# Bf706_DSP.net
KiCad netlist of a schematic drawn in Altium Designer
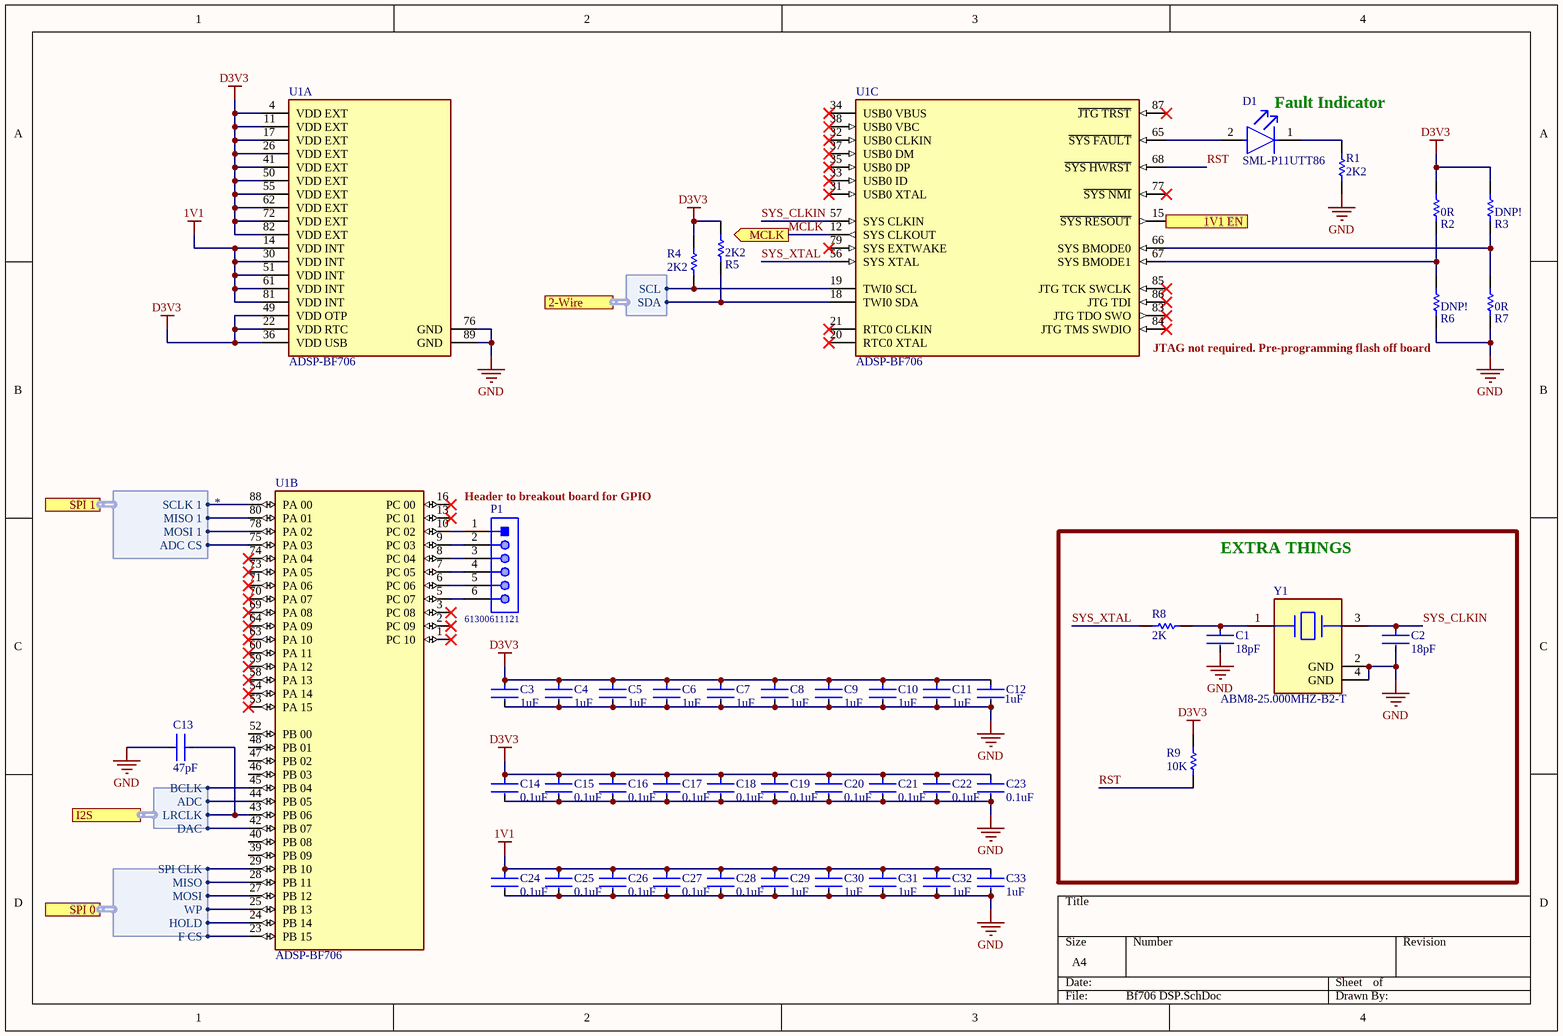
[diagram p0: Bf706 DSP.SchDoc]

(export (version "E")
  (design (tool "Eeschema 10.0.6"))
  (components
    (comp (ref "C1")
      (value "18pF")
      (footprint "FP-GRM15-MFG")
      (description "CAP CER 0.1UF 16V X7R 0402")
      (fields (field (name "MANUFACTURER PART NUMBER") "GRM155R71C104KA88D") (field (name "TOLERANCE") "10%"))
      (libsource (lib "Altium Content Vault") (part "236180d848d6139a670b325ea6854c9"))
    )
    (comp (ref "C2")
      (value "18pF")
      (footprint "FP-GRM15-MFG")
      (description "CAP CER 0.1UF 16V X7R 0402")
      (fields (field (name "MANUFACTURER PART NUMBER") "GRM155R71C104KA88D") (field (name "TOLERANCE") "10%"))
      (libsource (lib "Altium Content Vault") (part "236180d848d6139a670b325ea6854c9"))
    )
    (comp (ref "C3")
      (value "1uF")
      (footprint "FP-GRM15-MFG")
      (description "CAP CER 0.1UF 16V X7R 0402")
      (fields (field (name "MANUFACTURER PART NUMBER") "GRM155R71C104KA88D") (field (name "TOLERANCE") "10%"))
      (libsource (lib "Altium Content Vault") (part "236180d848d6139a670b325ea6854c9"))
    )
    (comp (ref "C4")
      (value "1uF")
      (footprint "FP-GRM15-MFG")
      (description "CAP CER 0.1UF 16V X7R 0402")
      (fields (field (name "MANUFACTURER PART NUMBER") "GRM155R71C104KA88D") (field (name "TOLERANCE") "10%"))
      (libsource (lib "Altium Content Vault") (part "236180d848d6139a670b325ea6854c9"))
    )
    (comp (ref "C5")
      (value "1uF")
      (footprint "FP-GRM15-MFG")
      (description "CAP CER 0.1UF 16V X7R 0402")
      (fields (field (name "MANUFACTURER PART NUMBER") "GRM155R71C104KA88D") (field (name "TOLERANCE") "10%"))
      (libsource (lib "Altium Content Vault") (part "236180d848d6139a670b325ea6854c9"))
    )
    (comp (ref "C6")
      (value "1uF")
      (footprint "FP-GRM15-MFG")
      (description "CAP CER 0.1UF 16V X7R 0402")
      (fields (field (name "MANUFACTURER PART NUMBER") "GRM155R71C104KA88D") (field (name "TOLERANCE") "10%"))
      (libsource (lib "Altium Content Vault") (part "236180d848d6139a670b325ea6854c9"))
    )
    (comp (ref "C7")
      (value "1uF")
      (footprint "FP-GRM15-MFG")
      (description "CAP CER 0.1UF 16V X7R 0402")
      (fields (field (name "MANUFACTURER PART NUMBER") "GRM155R71C104KA88D") (field (name "TOLERANCE") "10%"))
      (libsource (lib "Altium Content Vault") (part "236180d848d6139a670b325ea6854c9"))
    )
    (comp (ref "C8")
      (value "1uF")
      (footprint "FP-GRM15-MFG")
      (description "CAP CER 0.1UF 16V X7R 0402")
      (fields (field (name "MANUFACTURER PART NUMBER") "GRM155R71C104KA88D") (field (name "TOLERANCE") "10%"))
      (libsource (lib "Altium Content Vault") (part "236180d848d6139a670b325ea6854c9"))
    )
    (comp (ref "C9")
      (value "1uF")
      (footprint "FP-GRM15-MFG")
      (description "CAP CER 0.1UF 16V X7R 0402")
      (fields (field (name "MANUFACTURER PART NUMBER") "GRM155R71C104KA88D") (field (name "TOLERANCE") "10%"))
      (libsource (lib "Altium Content Vault") (part "236180d848d6139a670b325ea6854c9"))
    )
    (comp (ref "C10")
      (value "1uF")
      (footprint "FP-GRM15-MFG")
      (description "CAP CER 0.1UF 16V X7R 0402")
      (fields (field (name "MANUFACTURER PART NUMBER") "GRM155R71C104KA88D") (field (name "TOLERANCE") "10%"))
      (libsource (lib "Altium Content Vault") (part "236180d848d6139a670b325ea6854c9"))
    )
    (comp (ref "C11")
      (value "1uF")
      (footprint "FP-GRM15-MFG")
      (description "CAP CER 0.1UF 16V X7R 0402")
      (fields (field (name "MANUFACTURER PART NUMBER") "GRM155R71C104KA88D") (field (name "TOLERANCE") "10%"))
      (libsource (lib "Altium Content Vault") (part "236180d848d6139a670b325ea6854c9"))
    )
    (comp (ref "C12")
      (value "1uF")
      (footprint "FP-GRM15-MFG")
      (description "CAP CER 0.1UF 16V X7R 0402")
      (fields (field (name "MANUFACTURER PART NUMBER") "GRM155R71C104KA88D") (field (name "TOLERANCE") "10%"))
      (libsource (lib "Altium Content Vault") (part "236180d848d6139a670b325ea6854c9"))
    )
    (comp (ref "C13")
      (value "47pF")
      (footprint "FP-GRM15-MFG")
      (description "CAP CER 0.1UF 16V X7R 0402")
      (fields (field (name "MANUFACTURER PART NUMBER") "GRM155R71C104KA88D") (field (name "TOLERANCE") "10%"))
      (libsource (lib "Altium Content Vault") (part "236180d848d6139a670b325ea6854c9"))
    )
    (comp (ref "C14")
      (value "0.1uF")
      (footprint "FP-GRM15-MFG")
      (description "CAP CER 0.1UF 16V X7R 0402")
      (fields (field (name "MANUFACTURER PART NUMBER") "GRM155R71C104KA88D") (field (name "TOLERANCE") "10%"))
      (libsource (lib "Altium Content Vault") (part "236180d848d6139a670b325ea6854c9"))
    )
    (comp (ref "C15")
      (value "0.1uF")
      (footprint "FP-GRM15-MFG")
      (description "CAP CER 0.1UF 16V X7R 0402")
      (fields (field (name "MANUFACTURER PART NUMBER") "GRM155R71C104KA88D") (field (name "TOLERANCE") "10%"))
      (libsource (lib "Altium Content Vault") (part "236180d848d6139a670b325ea6854c9"))
    )
    (comp (ref "C16")
      (value "0.1uF")
      (footprint "FP-GRM15-MFG")
      (description "CAP CER 0.1UF 16V X7R 0402")
      (fields (field (name "MANUFACTURER PART NUMBER") "GRM155R71C104KA88D") (field (name "TOLERANCE") "10%"))
      (libsource (lib "Altium Content Vault") (part "236180d848d6139a670b325ea6854c9"))
    )
    (comp (ref "C17")
      (value "0.1uF")
      (footprint "FP-GRM15-MFG")
      (description "CAP CER 0.1UF 16V X7R 0402")
      (fields (field (name "MANUFACTURER PART NUMBER") "GRM155R71C104KA88D") (field (name "TOLERANCE") "10%"))
      (libsource (lib "Altium Content Vault") (part "236180d848d6139a670b325ea6854c9"))
    )
    (comp (ref "C18")
      (value "0.1uF")
      (footprint "FP-GRM15-MFG")
      (description "CAP CER 0.1UF 16V X7R 0402")
      (fields (field (name "MANUFACTURER PART NUMBER") "GRM155R71C104KA88D") (field (name "TOLERANCE") "10%"))
      (libsource (lib "Altium Content Vault") (part "236180d848d6139a670b325ea6854c9"))
    )
    (comp (ref "C19")
      (value "0.1uF")
      (footprint "FP-GRM15-MFG")
      (description "CAP CER 0.1UF 16V X7R 0402")
      (fields (field (name "MANUFACTURER PART NUMBER") "GRM155R71C104KA88D") (field (name "TOLERANCE") "10%"))
      (libsource (lib "Altium Content Vault") (part "236180d848d6139a670b325ea6854c9"))
    )
    (comp (ref "C20")
      (value "0.1uF")
      (footprint "FP-GRM15-MFG")
      (description "CAP CER 0.1UF 16V X7R 0402")
      (fields (field (name "MANUFACTURER PART NUMBER") "GRM155R71C104KA88D") (field (name "TOLERANCE") "10%"))
      (libsource (lib "Altium Content Vault") (part "236180d848d6139a670b325ea6854c9"))
    )
    (comp (ref "C21")
      (value "0.1uF")
      (footprint "FP-GRM15-MFG")
      (description "CAP CER 0.1UF 16V X7R 0402")
      (fields (field (name "MANUFACTURER PART NUMBER") "GRM155R71C104KA88D") (field (name "TOLERANCE") "10%"))
      (libsource (lib "Altium Content Vault") (part "236180d848d6139a670b325ea6854c9"))
    )
    (comp (ref "C22")
      (value "0.1uF")
      (footprint "FP-GRM15-MFG")
      (description "CAP CER 0.1UF 16V X7R 0402")
      (fields (field (name "MANUFACTURER PART NUMBER") "GRM155R71C104KA88D") (field (name "TOLERANCE") "10%"))
      (libsource (lib "Altium Content Vault") (part "236180d848d6139a670b325ea6854c9"))
    )
    (comp (ref "C23")
      (value "0.1uF")
      (footprint "FP-GRM15-MFG")
      (description "CAP CER 0.1UF 16V X7R 0402")
      (fields (field (name "MANUFACTURER PART NUMBER") "GRM155R71C104KA88D") (field (name "TOLERANCE") "10%"))
      (libsource (lib "Altium Content Vault") (part "236180d848d6139a670b325ea6854c9"))
    )
    (comp (ref "C24")
      (value "0.1uF")
      (footprint "FP-GRM15-MFG")
      (description "CAP CER 0.1UF 16V X7R 0402")
      (fields (field (name "MANUFACTURER PART NUMBER") "GRM155R71C104KA88D") (field (name "TOLERANCE") "10%"))
      (libsource (lib "Altium Content Vault") (part "236180d848d6139a670b325ea6854c9"))
    )
    (comp (ref "C25")
      (value "0.1uF")
      (footprint "FP-GRM15-MFG")
      (description "CAP CER 0.1UF 16V X7R 0402")
      (fields (field (name "MANUFACTURER PART NUMBER") "GRM155R71C104KA88D") (field (name "TOLERANCE") "10%"))
      (libsource (lib "Altium Content Vault") (part "236180d848d6139a670b325ea6854c9"))
    )
    (comp (ref "C26")
      (value "0.1uF")
      (footprint "FP-GRM15-MFG")
      (description "CAP CER 0.1UF 16V X7R 0402")
      (fields (field (name "MANUFACTURER PART NUMBER") "GRM155R71C104KA88D") (field (name "TOLERANCE") "10%"))
      (libsource (lib "Altium Content Vault") (part "236180d848d6139a670b325ea6854c9"))
    )
    (comp (ref "C27")
      (value "0.1uF")
      (footprint "FP-GRM15-MFG")
      (description "CAP CER 0.1UF 16V X7R 0402")
      (fields (field (name "MANUFACTURER PART NUMBER") "GRM155R71C104KA88D") (field (name "TOLERANCE") "10%"))
      (libsource (lib "Altium Content Vault") (part "236180d848d6139a670b325ea6854c9"))
    )
    (comp (ref "C28")
      (value "0.1uF")
      (footprint "FP-GRM15-MFG")
      (description "CAP CER 0.1UF 16V X7R 0402")
      (fields (field (name "MANUFACTURER PART NUMBER") "GRM155R71C104KA88D") (field (name "TOLERANCE") "10%"))
      (libsource (lib "Altium Content Vault") (part "236180d848d6139a670b325ea6854c9"))
    )
    (comp (ref "C29")
      (value "1uF")
      (footprint "FP-GRM15-MFG")
      (description "CAP CER 0.1UF 16V X7R 0402")
      (fields (field (name "MANUFACTURER PART NUMBER") "GRM155R71C104KA88D") (field (name "TOLERANCE") "10%"))
      (libsource (lib "Altium Content Vault") (part "236180d848d6139a670b325ea6854c9"))
    )
    (comp (ref "C30")
      (value "1uF")
      (footprint "FP-GRM15-MFG")
      (description "CAP CER 0.1UF 16V X7R 0402")
      (fields (field (name "MANUFACTURER PART NUMBER") "GRM155R71C104KA88D") (field (name "TOLERANCE") "10%"))
      (libsource (lib "Altium Content Vault") (part "236180d848d6139a670b325ea6854c9"))
    )
    (comp (ref "C31")
      (value "1uF")
      (footprint "FP-GRM15-MFG")
      (description "CAP CER 0.1UF 16V X7R 0402")
      (fields (field (name "MANUFACTURER PART NUMBER") "GRM155R71C104KA88D") (field (name "TOLERANCE") "10%"))
      (libsource (lib "Altium Content Vault") (part "236180d848d6139a670b325ea6854c9"))
    )
    (comp (ref "C32")
      (value "1uF")
      (footprint "FP-GRM15-MFG")
      (description "CAP CER 0.1UF 16V X7R 0402")
      (fields (field (name "MANUFACTURER PART NUMBER") "GRM155R71C104KA88D") (field (name "TOLERANCE") "10%"))
      (libsource (lib "Altium Content Vault") (part "236180d848d6139a670b325ea6854c9"))
    )
    (comp (ref "C33")
      (value "1uF")
      (footprint "FP-GRM15-MFG")
      (description "CAP CER 0.1UF 16V X7R 0402")
      (fields (field (name "MANUFACTURER PART NUMBER") "GRM155R71C104KA88D") (field (name "TOLERANCE") "10%"))
      (libsource (lib "Altium Content Vault") (part "236180d848d6139a670b325ea6854c9"))
    )
    (comp (ref "D1")
      (value "SML-P11UTT86")
      (footprint "FP-SML-P11UTT86-MFG")
      (description "LED RED CLEAR 1006 SMD")
      (libsource (lib "Altium Content Vault") (part "8706943c75ba83719d021d2fdc84c58"))
    )
    (comp (ref "P1")
      (value "61300611121")
      (footprint "61300611121")
      (description "THT Vertical Pin Header WR-PHD, Pitch 2.54 mm, Single Row, 6 pins")
      (fields (field (name "MANUFACTURER") "Wurth Elektronik") (field (name "PUBLISHER") "WurthElektronik"))
      (libsource (lib "Altium Content Vault") (part "WE-CN-1P-M-R6"))
    )
    (comp (ref "R1")
      (value "2K2")
      (footprint "RESC1005X40X25LL05T05")
      (description "Chip Resistor, 0 Ohm, 0.1 W, -55 to 155 degC, 0402 (1005 Metric), RoHS, Tape and Reel")
      (fields (field (name "MANUFACTURER") "Panasonic") (field (name "TOLERANCE") "5%"))
      (libsource (lib "Altium Content Vault") (part "RES-2"))
    )
    (comp (ref "R2")
      (value "0R")
      (footprint "RESC1005X40X25LL05T05")
      (description "Chip Resistor, 0 Ohm, 0.1 W, -55 to 155 degC, 0402 (1005 Metric), RoHS, Tape and Reel")
      (fields (field (name "MANUFACTURER") "Panasonic") (field (name "TOLERANCE") "5%"))
      (libsource (lib "Altium Content Vault") (part "RES-2"))
    )
    (comp (ref "R3")
      (value "DNP!")
      (footprint "RESC1005X40X25LL05T05")
      (description "Chip Resistor, 0 Ohm, 0.1 W, -55 to 155 degC, 0402 (1005 Metric), RoHS, Tape and Reel")
      (fields (field (name "MANUFACTURER") "Panasonic") (field (name "TOLERANCE") "5%"))
      (libsource (lib "Altium Content Vault") (part "RES-2"))
    )
    (comp (ref "R4")
      (value "2K2")
      (footprint "RESC1005X40X25LL05T05")
      (description "Chip Resistor, 0 Ohm, 0.1 W, -55 to 155 degC, 0402 (1005 Metric), RoHS, Tape and Reel")
      (fields (field (name "MANUFACTURER") "Panasonic") (field (name "TOLERANCE") "5%"))
      (libsource (lib "Altium Content Vault") (part "RES-2"))
    )
    (comp (ref "R5")
      (value "2K2")
      (footprint "RESC1005X40X25LL05T05")
      (description "Chip Resistor, 0 Ohm, 0.1 W, -55 to 155 degC, 0402 (1005 Metric), RoHS, Tape and Reel")
      (fields (field (name "MANUFACTURER") "Panasonic") (field (name "TOLERANCE") "5%"))
      (libsource (lib "Altium Content Vault") (part "RES-2"))
    )
    (comp (ref "R6")
      (value "DNP!")
      (footprint "RESC1005X40X25LL05T05")
      (description "Chip Resistor, 0 Ohm, 0.1 W, -55 to 155 degC, 0402 (1005 Metric), RoHS, Tape and Reel")
      (fields (field (name "MANUFACTURER") "Panasonic") (field (name "TOLERANCE") "5%"))
      (libsource (lib "Altium Content Vault") (part "RES-2"))
    )
    (comp (ref "R7")
      (value "0R")
      (footprint "RESC1005X40X25LL05T05")
      (description "Chip Resistor, 0 Ohm, 0.1 W, -55 to 155 degC, 0402 (1005 Metric), RoHS, Tape and Reel")
      (fields (field (name "MANUFACTURER") "Panasonic") (field (name "TOLERANCE") "5%"))
      (libsource (lib "Altium Content Vault") (part "RES-2"))
    )
    (comp (ref "R8")
      (value "2K")
      (footprint "RESC1005X40X25LL05T05")
      (description "Chip Resistor, 0 Ohm, 0.1 W, -55 to 155 degC, 0402 (1005 Metric), RoHS, Tape and Reel")
      (fields (field (name "MANUFACTURER") "Panasonic") (field (name "TOLERANCE") "5%"))
      (libsource (lib "Altium Content Vault") (part "RES-2"))
    )
    (comp (ref "R9")
      (value "10K")
      (footprint "RESC1005X40X25LL05T05")
      (description "Chip Resistor, 0 Ohm, 0.1 W, -55 to 155 degC, 0402 (1005 Metric), RoHS, Tape and Reel")
      (fields (field (name "MANUFACTURER") "Panasonic") (field (name "TOLERANCE") "5%"))
      (libsource (lib "Altium Content Vault") (part "RES-2"))
    )
    (comp (ref "U1")
      (value "ADSP-BF706")
      (footprint "FP-CP-88-8-IPC_C")
      (description "IC DSP LP 128KB L2SR 88LFCSP")
      (libsource (lib "Altium Content Vault") (part "f148b48c6e4e4aed1bc29808ef88166"))
    )
    (comp (ref "Y1")
      (value "ABM8-25.000MHZ-B2-T")
      (footprint "FP-ABM8-MFG")
      (description "Crystal 25MHz ±20ppm 18pF SMD-4 3.2mm x 2.5mm")
      (fields (field (name "TOLERANCE") "20ppm"))
      (libsource (lib "Altium Content Vault") (part "dfdb7f9a12507849fb681da9a70121c"))
    )
  )
  (nets
    (net (code "6") (name "/1V1 EN") (class "Default")
      (node (ref "U1") (pin "15") (pinfunction "~{SYS_RESOUT}_15") (pintype "output"))
    )
    (net (code "7") (name "/ADC") (class "Default")
      (node (ref "U1") (pin "44") (pinfunction "PB_05_44") (pintype "bidirectional"))
    )
    (net (code "8") (name "/ADC CS") (class "Default")
      (node (ref "U1") (pin "75") (pinfunction "PA_03_75") (pintype "bidirectional"))
    )
    (net (code "9") (name "/BCLK") (class "Default")
      (node (ref "U1") (pin "45") (pinfunction "PB_04_45") (pintype "bidirectional"))
    )
    (net (code "10") (name "/DAC") (class "Default")
      (node (ref "U1") (pin "42") (pinfunction "PB_07_42") (pintype "bidirectional"))
    )
    (net (code "11") (name "/F CS") (class "Default")
      (node (ref "U1") (pin "23") (pinfunction "PB_15_23") (pintype "bidirectional"))
    )
    (net (code "12") (name "/HOLD") (class "Default")
      (node (ref "U1") (pin "24") (pinfunction "PB_14_24") (pintype "bidirectional"))
    )
    (net (code "13") (name "/LRCLK") (class "Default")
      (node (ref "C13") (pin "2") (pinfunction "2_2") (pintype "passive"))
      (node (ref "U1") (pin "43") (pinfunction "PB_06_43") (pintype "bidirectional"))
    )
    (net (code "14") (name "/MCLK") (class "Default")
      (node (ref "U1") (pin "12") (pinfunction "SYS_CLKOUT_12") (pintype "output"))
    )
    (net (code "15") (name "/MISO") (class "Default")
      (node (ref "U1") (pin "28") (pinfunction "PB_11_28") (pintype "bidirectional"))
    )
    (net (code "16") (name "/MISO 1") (class "Default")
      (node (ref "U1") (pin "80") (pinfunction "PA_01_80") (pintype "bidirectional"))
    )
    (net (code "17") (name "/MOSI") (class "Default")
      (node (ref "U1") (pin "27") (pinfunction "PB_12_27") (pintype "bidirectional"))
    )
    (net (code "18") (name "/MOSI 1") (class "Default")
      (node (ref "U1") (pin "78") (pinfunction "PA_02_78") (pintype "bidirectional"))
    )
    (net (code "19") (name "/RST") (class "Default")
      (node (ref "R9") (pin "1") (pinfunction "1_1") (pintype "passive"))
      (node (ref "U1") (pin "68") (pinfunction "~{SYS_HWRST}_68") (pintype "input"))
    )
    (net (code "20") (name "/SCL") (class "Default")
      (node (ref "R4") (pin "1") (pinfunction "1_1") (pintype "passive"))
      (node (ref "U1") (pin "19") (pinfunction "TWI0_SCL_19") (pintype "passive"))
    )
    (net (code "21") (name "/SCLK 1") (class "Default")
      (node (ref "U1") (pin "88") (pinfunction "PA_00_88") (pintype "bidirectional"))
    )
    (net (code "22") (name "/SDA") (class "Default")
      (node (ref "R5") (pin "1") (pinfunction "1_1") (pintype "passive"))
      (node (ref "U1") (pin "18") (pinfunction "TWI0_SDA_18") (pintype "passive"))
    )
    (net (code "23") (name "/SPI CLK") (class "Default")
      (node (ref "U1") (pin "29") (pinfunction "PB_10_29") (pintype "bidirectional"))
    )
    (net (code "24") (name "/SYS_CLKIN") (class "Default")
      (node (ref "C2") (pin "2") (pinfunction "2_2") (pintype "passive"))
      (node (ref "U1") (pin "57") (pinfunction "SYS_CLKIN_57") (pintype "input"))
      (node (ref "Y1") (pin "3") (pinfunction "3_3") (pintype "passive"))
    )
    (net (code "25") (name "/SYS_XTAL") (class "Default")
      (node (ref "R8") (pin "2") (pinfunction "2_2") (pintype "passive"))
      (node (ref "U1") (pin "56") (pinfunction "SYS_XTAL_56") (pintype "input"))
    )
    (net (code "26") (name "/WP") (class "Default")
      (node (ref "U1") (pin "25") (pinfunction "PB_13_25") (pintype "bidirectional"))
    )
    (net (code "31") (name "1V1") (class "Default")
      (node (ref "C24") (pin "2") (pinfunction "2_2") (pintype "passive"))
      (node (ref "C25") (pin "2") (pinfunction "2_2") (pintype "passive"))
      (node (ref "C26") (pin "2") (pinfunction "2_2") (pintype "passive"))
      (node (ref "C27") (pin "2") (pinfunction "2_2") (pintype "passive"))
      (node (ref "C28") (pin "2") (pinfunction "2_2") (pintype "passive"))
      (node (ref "C29") (pin "2") (pinfunction "2_2") (pintype "passive"))
      (node (ref "C30") (pin "2") (pinfunction "2_2") (pintype "passive"))
      (node (ref "C31") (pin "2") (pinfunction "2_2") (pintype "passive"))
      (node (ref "C32") (pin "2") (pinfunction "2_2") (pintype "passive"))
      (node (ref "C33") (pin "2") (pinfunction "2_2") (pintype "passive"))
      (node (ref "U1") (pin "14") (pinfunction "VDD_INT_14") (pintype "power_in"))
      (node (ref "U1") (pin "30") (pinfunction "VDD_INT_30") (pintype "power_in"))
      (node (ref "U1") (pin "51") (pinfunction "VDD_INT_51") (pintype "power_in"))
      (node (ref "U1") (pin "61") (pinfunction "VDD_INT_61") (pintype "power_in"))
      (node (ref "U1") (pin "81") (pinfunction "VDD_INT_81") (pintype "power_in"))
    )
    (net (code "32") (name "D3V3") (class "Default")
      (node (ref "C10") (pin "2") (pinfunction "2_2") (pintype "passive"))
      (node (ref "C11") (pin "2") (pinfunction "2_2") (pintype "passive"))
      (node (ref "C12") (pin "2") (pinfunction "2_2") (pintype "passive"))
      (node (ref "C14") (pin "2") (pinfunction "2_2") (pintype "passive"))
      (node (ref "C15") (pin "2") (pinfunction "2_2") (pintype "passive"))
      (node (ref "C16") (pin "2") (pinfunction "2_2") (pintype "passive"))
      (node (ref "C17") (pin "2") (pinfunction "2_2") (pintype "passive"))
      (node (ref "C18") (pin "2") (pinfunction "2_2") (pintype "passive"))
      (node (ref "C19") (pin "2") (pinfunction "2_2") (pintype "passive"))
      (node (ref "C20") (pin "2") (pinfunction "2_2") (pintype "passive"))
      (node (ref "C21") (pin "2") (pinfunction "2_2") (pintype "passive"))
      (node (ref "C22") (pin "2") (pinfunction "2_2") (pintype "passive"))
      (node (ref "C23") (pin "2") (pinfunction "2_2") (pintype "passive"))
      (node (ref "C3") (pin "2") (pinfunction "2_2") (pintype "passive"))
      (node (ref "C4") (pin "2") (pinfunction "2_2") (pintype "passive"))
      (node (ref "C5") (pin "2") (pinfunction "2_2") (pintype "passive"))
      (node (ref "C6") (pin "2") (pinfunction "2_2") (pintype "passive"))
      (node (ref "C7") (pin "2") (pinfunction "2_2") (pintype "passive"))
      (node (ref "C8") (pin "2") (pinfunction "2_2") (pintype "passive"))
      (node (ref "C9") (pin "2") (pinfunction "2_2") (pintype "passive"))
      (node (ref "R2") (pin "2") (pinfunction "2_2") (pintype "passive"))
      (node (ref "R3") (pin "2") (pinfunction "2_2") (pintype "passive"))
      (node (ref "R4") (pin "2") (pinfunction "2_2") (pintype "passive"))
      (node (ref "R5") (pin "2") (pinfunction "2_2") (pintype "passive"))
      (node (ref "R9") (pin "2") (pinfunction "2_2") (pintype "passive"))
      (node (ref "U1") (pin "11") (pinfunction "VDD_EXT_11") (pintype "power_in"))
      (node (ref "U1") (pin "17") (pinfunction "VDD_EXT_17") (pintype "power_in"))
      (node (ref "U1") (pin "22") (pinfunction "VDD_RTC_22") (pintype "power_in"))
      (node (ref "U1") (pin "26") (pinfunction "VDD_EXT_26") (pintype "power_in"))
      (node (ref "U1") (pin "36") (pinfunction "VDD_USB_36") (pintype "power_in"))
      (node (ref "U1") (pin "4") (pinfunction "VDD_EXT_4") (pintype "power_in"))
      (node (ref "U1") (pin "41") (pinfunction "VDD_EXT_41") (pintype "power_in"))
      (node (ref "U1") (pin "49") (pinfunction "VDD_OTP_49") (pintype "power_in"))
      (node (ref "U1") (pin "50") (pinfunction "VDD_EXT_50") (pintype "power_in"))
      (node (ref "U1") (pin "55") (pinfunction "VDD_EXT_55") (pintype "power_in"))
      (node (ref "U1") (pin "62") (pinfunction "VDD_EXT_62") (pintype "power_in"))
      (node (ref "U1") (pin "72") (pinfunction "VDD_EXT_72") (pintype "power_in"))
      (node (ref "U1") (pin "82") (pinfunction "VDD_EXT_82") (pintype "power_in"))
    )
    (net (code "33") (name "GND") (class "Default")
      (node (ref "C1") (pin "1") (pinfunction "1_1") (pintype "passive"))
      (node (ref "C10") (pin "1") (pinfunction "1_1") (pintype "passive"))
      (node (ref "C11") (pin "1") (pinfunction "1_1") (pintype "passive"))
      (node (ref "C12") (pin "1") (pinfunction "1_1") (pintype "passive"))
      (node (ref "C13") (pin "1") (pinfunction "1_1") (pintype "passive"))
      (node (ref "C14") (pin "1") (pinfunction "1_1") (pintype "passive"))
      (node (ref "C15") (pin "1") (pinfunction "1_1") (pintype "passive"))
      (node (ref "C16") (pin "1") (pinfunction "1_1") (pintype "passive"))
      (node (ref "C17") (pin "1") (pinfunction "1_1") (pintype "passive"))
      (node (ref "C18") (pin "1") (pinfunction "1_1") (pintype "passive"))
      (node (ref "C19") (pin "1") (pinfunction "1_1") (pintype "passive"))
      (node (ref "C2") (pin "1") (pinfunction "1_1") (pintype "passive"))
      (node (ref "C20") (pin "1") (pinfunction "1_1") (pintype "passive"))
      (node (ref "C21") (pin "1") (pinfunction "1_1") (pintype "passive"))
      (node (ref "C22") (pin "1") (pinfunction "1_1") (pintype "passive"))
      (node (ref "C23") (pin "1") (pinfunction "1_1") (pintype "passive"))
      (node (ref "C24") (pin "1") (pinfunction "1_1") (pintype "passive"))
      (node (ref "C25") (pin "1") (pinfunction "1_1") (pintype "passive"))
      (node (ref "C26") (pin "1") (pinfunction "1_1") (pintype "passive"))
      (node (ref "C27") (pin "1") (pinfunction "1_1") (pintype "passive"))
      (node (ref "C28") (pin "1") (pinfunction "1_1") (pintype "passive"))
      (node (ref "C29") (pin "1") (pinfunction "1_1") (pintype "passive"))
      (node (ref "C3") (pin "1") (pinfunction "1_1") (pintype "passive"))
      (node (ref "C30") (pin "1") (pinfunction "1_1") (pintype "passive"))
      (node (ref "C31") (pin "1") (pinfunction "1_1") (pintype "passive"))
      (node (ref "C32") (pin "1") (pinfunction "1_1") (pintype "passive"))
      (node (ref "C33") (pin "1") (pinfunction "1_1") (pintype "passive"))
      (node (ref "C4") (pin "1") (pinfunction "1_1") (pintype "passive"))
      (node (ref "C5") (pin "1") (pinfunction "1_1") (pintype "passive"))
      (node (ref "C6") (pin "1") (pinfunction "1_1") (pintype "passive"))
      (node (ref "C7") (pin "1") (pinfunction "1_1") (pintype "passive"))
      (node (ref "C8") (pin "1") (pinfunction "1_1") (pintype "passive"))
      (node (ref "C9") (pin "1") (pinfunction "1_1") (pintype "passive"))
      (node (ref "R1") (pin "1") (pinfunction "1_1") (pintype "passive"))
      (node (ref "R6") (pin "1") (pinfunction "1_1") (pintype "passive"))
      (node (ref "R7") (pin "1") (pinfunction "1_1") (pintype "passive"))
      (node (ref "U1") (pin "76") (pinfunction "GND_76") (pintype "power_in"))
      (node (ref "U1") (pin "89") (pinfunction "GND_89") (pintype "power_in"))
      (node (ref "Y1") (pin "2") (pinfunction "GND_2") (pintype "power_in"))
      (node (ref "Y1") (pin "4") (pinfunction "GND_4") (pintype "power_in"))
    )
    (net (code "34") (name "Net-(C1-Pad2)") (class "Default")
      (node (ref "C1") (pin "2") (pinfunction "2_2") (pintype "passive"))
      (node (ref "R8") (pin "1") (pinfunction "1_1") (pintype "passive"))
      (node (ref "Y1") (pin "1") (pinfunction "1_1") (pintype "passive"))
    )
    (net (code "35") (name "Net-(D1-A)") (class "Default")
      (node (ref "D1") (pin "2") (pinfunction "A_2") (pintype "passive"))
      (node (ref "U1") (pin "65") (pinfunction "~{SYS_FAULT}_65") (pintype "input"))
    )
    (net (code "36") (name "Net-(D1-C)") (class "Default")
      (node (ref "D1") (pin "1") (pinfunction "C_1") (pintype "passive"))
      (node (ref "R1") (pin "2") (pinfunction "2_2") (pintype "passive"))
    )
    (net (code "37") (name "Net-(U1B-PC_02)") (class "Default")
      (node (ref "P1") (pin "1") (pinfunction "1_1") (pintype "passive"))
      (node (ref "U1") (pin "10") (pinfunction "PC_02_10") (pintype "bidirectional"))
    )
    (net (code "38") (name "Net-(U1B-PC_03)") (class "Default")
      (node (ref "P1") (pin "2") (pinfunction "2_2") (pintype "passive"))
      (node (ref "U1") (pin "9") (pinfunction "PC_03_9") (pintype "bidirectional"))
    )
    (net (code "39") (name "Net-(U1B-PC_04)") (class "Default")
      (node (ref "P1") (pin "3") (pinfunction "3_3") (pintype "passive"))
      (node (ref "U1") (pin "8") (pinfunction "PC_04_8") (pintype "bidirectional"))
    )
    (net (code "40") (name "Net-(U1B-PC_05)") (class "Default")
      (node (ref "P1") (pin "4") (pinfunction "4_4") (pintype "passive"))
      (node (ref "U1") (pin "7") (pinfunction "PC_05_7") (pintype "bidirectional"))
    )
    (net (code "41") (name "Net-(U1B-PC_06)") (class "Default")
      (node (ref "P1") (pin "5") (pinfunction "5_5") (pintype "passive"))
      (node (ref "U1") (pin "6") (pinfunction "PC_06_6") (pintype "bidirectional"))
    )
    (net (code "42") (name "Net-(U1B-PC_07)") (class "Default")
      (node (ref "P1") (pin "6") (pinfunction "6_6") (pintype "passive"))
      (node (ref "U1") (pin "5") (pinfunction "PC_07_5") (pintype "bidirectional"))
    )
    (net (code "43") (name "Net-(U1C-SYS_BMODE0)") (class "Default")
      (node (ref "R3") (pin "1") (pinfunction "1_1") (pintype "passive"))
      (node (ref "R7") (pin "2") (pinfunction "2_2") (pintype "passive"))
      (node (ref "U1") (pin "66") (pinfunction "SYS_BMODE0_66") (pintype "input"))
    )
    (net (code "44") (name "Net-(U1C-SYS_BMODE1)") (class "Default")
      (node (ref "R2") (pin "1") (pinfunction "1_1") (pintype "passive"))
      (node (ref "R6") (pin "2") (pinfunction "2_2") (pintype "passive"))
      (node (ref "U1") (pin "67") (pinfunction "SYS_BMODE1_67") (pintype "input"))
    )
    (net (code "45") (name "unconnected-(U1B-PA_04-Pad74)") (class "Default")
      (node (ref "U1") (pin "74") (pinfunction "PA_04_74") (pintype "bidirectional+no_connect"))
    )
    (net (code "46") (name "unconnected-(U1B-PA_05-Pad73)") (class "Default")
      (node (ref "U1") (pin "73") (pinfunction "PA_05_73") (pintype "bidirectional+no_connect"))
    )
    (net (code "47") (name "unconnected-(U1B-PA_06-Pad71)") (class "Default")
      (node (ref "U1") (pin "71") (pinfunction "PA_06_71") (pintype "bidirectional+no_connect"))
    )
    (net (code "48") (name "unconnected-(U1B-PA_07-Pad70)") (class "Default")
      (node (ref "U1") (pin "70") (pinfunction "PA_07_70") (pintype "bidirectional+no_connect"))
    )
    (net (code "49") (name "unconnected-(U1B-PA_08-Pad69)") (class "Default")
      (node (ref "U1") (pin "69") (pinfunction "PA_08_69") (pintype "bidirectional+no_connect"))
    )
    (net (code "50") (name "unconnected-(U1B-PA_09-Pad64)") (class "Default")
      (node (ref "U1") (pin "64") (pinfunction "PA_09_64") (pintype "bidirectional+no_connect"))
    )
    (net (code "51") (name "unconnected-(U1B-PA_10-Pad63)") (class "Default")
      (node (ref "U1") (pin "63") (pinfunction "PA_10_63") (pintype "bidirectional+no_connect"))
    )
    (net (code "52") (name "unconnected-(U1B-PA_11-Pad60)") (class "Default")
      (node (ref "U1") (pin "60") (pinfunction "PA_11_60") (pintype "bidirectional+no_connect"))
    )
    (net (code "53") (name "unconnected-(U1B-PA_12-Pad59)") (class "Default")
      (node (ref "U1") (pin "59") (pinfunction "PA_12_59") (pintype "bidirectional+no_connect"))
    )
    (net (code "54") (name "unconnected-(U1B-PA_13-Pad58)") (class "Default")
      (node (ref "U1") (pin "58") (pinfunction "PA_13_58") (pintype "bidirectional+no_connect"))
    )
    (net (code "55") (name "unconnected-(U1B-PA_14-Pad54)") (class "Default")
      (node (ref "U1") (pin "54") (pinfunction "PA_14_54") (pintype "bidirectional+no_connect"))
    )
    (net (code "56") (name "unconnected-(U1B-PA_15-Pad53)") (class "Default")
      (node (ref "U1") (pin "53") (pinfunction "PA_15_53") (pintype "bidirectional+no_connect"))
    )
    (net (code "57") (name "unconnected-(U1B-PB_00-Pad52)") (class "Default")
      (node (ref "U1") (pin "52") (pinfunction "PB_00_52") (pintype "bidirectional"))
    )
    (net (code "58") (name "unconnected-(U1B-PB_01-Pad48)") (class "Default")
      (node (ref "U1") (pin "48") (pinfunction "PB_01_48") (pintype "bidirectional"))
    )
    (net (code "59") (name "unconnected-(U1B-PB_02-Pad47)") (class "Default")
      (node (ref "U1") (pin "47") (pinfunction "PB_02_47") (pintype "bidirectional"))
    )
    (net (code "60") (name "unconnected-(U1B-PB_03-Pad46)") (class "Default")
      (node (ref "U1") (pin "46") (pinfunction "PB_03_46") (pintype "bidirectional"))
    )
    (net (code "61") (name "unconnected-(U1B-PB_08-Pad40)") (class "Default")
      (node (ref "U1") (pin "40") (pinfunction "PB_08_40") (pintype "bidirectional"))
    )
    (net (code "62") (name "unconnected-(U1B-PB_09-Pad39)") (class "Default")
      (node (ref "U1") (pin "39") (pinfunction "PB_09_39") (pintype "bidirectional"))
    )
    (net (code "63") (name "unconnected-(U1B-PC_00-Pad16)") (class "Default")
      (node (ref "U1") (pin "16") (pinfunction "PC_00_16") (pintype "bidirectional+no_connect"))
    )
    (net (code "64") (name "unconnected-(U1B-PC_01-Pad13)") (class "Default")
      (node (ref "U1") (pin "13") (pinfunction "PC_01_13") (pintype "bidirectional+no_connect"))
    )
    (net (code "65") (name "unconnected-(U1B-PC_08-Pad3)") (class "Default")
      (node (ref "U1") (pin "3") (pinfunction "PC_08_3") (pintype "bidirectional+no_connect"))
    )
    (net (code "66") (name "unconnected-(U1B-PC_09-Pad2)") (class "Default")
      (node (ref "U1") (pin "2") (pinfunction "PC_09_2") (pintype "bidirectional+no_connect"))
    )
    (net (code "67") (name "unconnected-(U1B-PC_10-Pad1)") (class "Default")
      (node (ref "U1") (pin "1") (pinfunction "PC_10_1") (pintype "bidirectional+no_connect"))
    )
    (net (code "68") (name "unconnected-(U1C-JTG_TCK_SWCLK-Pad85)") (class "Default")
      (node (ref "U1") (pin "85") (pinfunction "JTG_TCK_SWCLK_85") (pintype "input+no_connect"))
    )
    (net (code "69") (name "unconnected-(U1C-JTG_TDI-Pad86)") (class "Default")
      (node (ref "U1") (pin "86") (pinfunction "JTG_TDI_86") (pintype "input+no_connect"))
    )
    (net (code "70") (name "unconnected-(U1C-JTG_TDO_SWO-Pad83)") (class "Default")
      (node (ref "U1") (pin "83") (pinfunction "JTG_TDO_SWO_83") (pintype "output+no_connect"))
    )
    (net (code "71") (name "unconnected-(U1C-JTG_TMS_SWDIO-Pad84)") (class "Default")
      (node (ref "U1") (pin "84") (pinfunction "JTG_TMS_SWDIO_84") (pintype "input+no_connect"))
    )
    (net (code "72") (name "unconnected-(U1C-RTC0_CLKIN-Pad21)") (class "Default")
      (node (ref "U1") (pin "21") (pinfunction "RTC0_CLKIN_21") (pintype "passive+no_connect"))
    )
    (net (code "73") (name "unconnected-(U1C-RTC0_XTAL-Pad20)") (class "Default")
      (node (ref "U1") (pin "20") (pinfunction "RTC0_XTAL_20") (pintype "passive+no_connect"))
    )
    (net (code "74") (name "unconnected-(U1C-SYS_EXTWAKE-Pad79)") (class "Default")
      (node (ref "U1") (pin "79") (pinfunction "SYS_EXTWAKE_79") (pintype "input+no_connect"))
    )
    (net (code "75") (name "unconnected-(U1C-USB0_CLKIN-Pad32)") (class "Default")
      (node (ref "U1") (pin "32") (pinfunction "USB0_CLKIN_32") (pintype "input+no_connect"))
    )
    (net (code "76") (name "unconnected-(U1C-USB0_DM-Pad37)") (class "Default")
      (node (ref "U1") (pin "37") (pinfunction "USB0_DM_37") (pintype "input+no_connect"))
    )
    (net (code "77") (name "unconnected-(U1C-USB0_DP-Pad35)") (class "Default")
      (node (ref "U1") (pin "35") (pinfunction "USB0_DP_35") (pintype "input+no_connect"))
    )
    (net (code "78") (name "unconnected-(U1C-USB0_ID-Pad33)") (class "Default")
      (node (ref "U1") (pin "33") (pinfunction "USB0_ID_33") (pintype "input+no_connect"))
    )
    (net (code "79") (name "unconnected-(U1C-USB0_VBC-Pad38)") (class "Default")
      (node (ref "U1") (pin "38") (pinfunction "USB0_VBC_38") (pintype "input+no_connect"))
    )
    (net (code "80") (name "unconnected-(U1C-USB0_VBUS-Pad34)") (class "Default")
      (node (ref "U1") (pin "34") (pinfunction "USB0_VBUS_34") (pintype "power_in+no_connect"))
    )
    (net (code "81") (name "unconnected-(U1C-USB0_XTAL-Pad31)") (class "Default")
      (node (ref "U1") (pin "31") (pinfunction "USB0_XTAL_31") (pintype "input+no_connect"))
    )
    (net (code "82") (name "unconnected-(U1C-~{JTG_TRST}-Pad87)") (class "Default")
      (node (ref "U1") (pin "87") (pinfunction "~{JTG_TRST}_87") (pintype "input+no_connect"))
    )
    (net (code "83") (name "unconnected-(U1C-~{SYS_NMI}-Pad77)") (class "Default")
      (node (ref "U1") (pin "77") (pinfunction "~{SYS_NMI}_77") (pintype "input+no_connect"))
    )
  )
)
